# Controller_Board.net
KiCad netlist of a schematic drawn in EAGLE
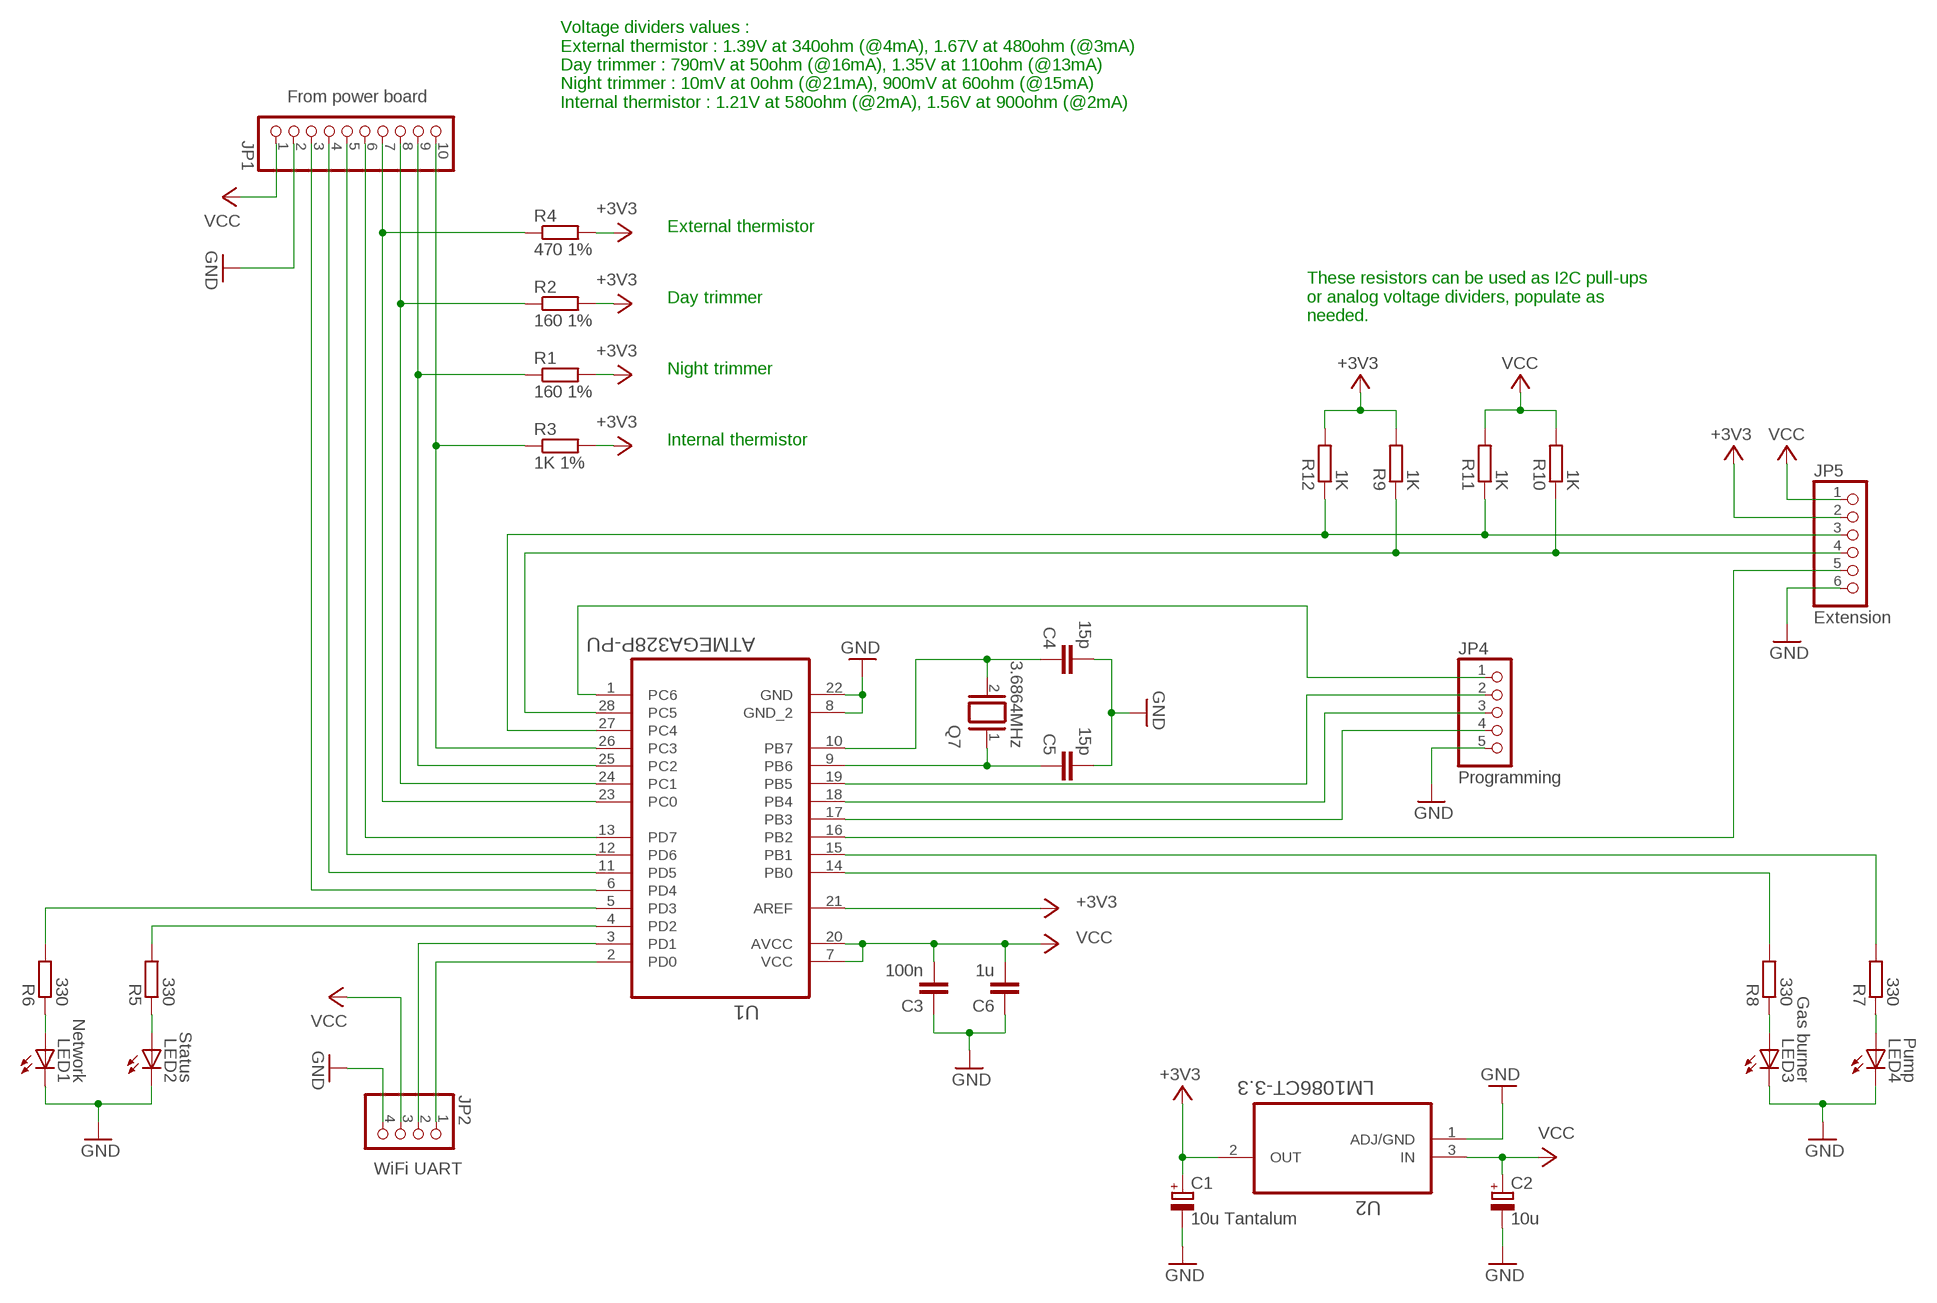
[diagram p0: schematic, sheet 1]

(export (version "E")
  (design (tool "Eeschema 10.0.6"))
  (components
    (comp (ref "C1")
      (value "10u Tantalum")
      (footprint "eagle-import:E2,5-7")
      (libsource (lib "eagle-import") (part "CPOL-EUE2.5-7"))
    )
    (comp (ref "C2")
      (value "10u")
      (footprint "eagle-import:E2,5-7")
      (libsource (lib "eagle-import") (part "CPOL-EUE2.5-7"))
    )
    (comp (ref "C3")
      (value "100n")
      (footprint "eagle-import:C050-035X075")
      (libsource (lib "eagle-import") (part "C-EU050-035X075"))
    )
    (comp (ref "C4")
      (value "15p")
      (footprint "eagle-import:C025-050X050")
      (libsource (lib "eagle-import") (part "rcl_334_C-EU025-050X050"))
    )
    (comp (ref "C5")
      (value "15p")
      (footprint "eagle-import:C025-050X050")
      (libsource (lib "eagle-import") (part "rcl_334_C-EU025-050X050"))
    )
    (comp (ref "C6")
      (value "1u")
      (footprint "eagle-import:C050-035X075")
      (libsource (lib "eagle-import") (part "C-EU050-035X075"))
    )
    (comp (ref "JP1")
      (value "From power board")
      (footprint "eagle-import:1X10")
      (libsource (lib "eagle-import") (part "PINHD-1X10"))
    )
    (comp (ref "JP2")
      (value "WiFi UART")
      (footprint "eagle-import:1X04")
      (libsource (lib "eagle-import") (part "PINHD-1X4"))
    )
    (comp (ref "JP4")
      (value "Programming")
      (footprint "eagle-import:1X05")
      (libsource (lib "eagle-import") (part "PINHD-1X5"))
    )
    (comp (ref "JP5")
      (value "Extension")
      (footprint "eagle-import:1X06")
      (libsource (lib "eagle-import") (part "PINHD-1X6"))
    )
    (comp (ref "LED1")
      (value "Network")
      (footprint "eagle-import:LED5MM")
      (libsource (lib "eagle-import") (part "LED5MM"))
    )
    (comp (ref "LED2")
      (value "Status")
      (footprint "eagle-import:LED5MM")
      (libsource (lib "eagle-import") (part "LED5MM"))
    )
    (comp (ref "LED3")
      (value "Gas burner")
      (footprint "eagle-import:LED5MM")
      (libsource (lib "eagle-import") (part "LED5MM"))
    )
    (comp (ref "LED4")
      (value "Pump")
      (footprint "eagle-import:LED5MM")
      (libsource (lib "eagle-import") (part "LED5MM"))
    )
    (comp (ref "Q7")
      (value "3.6864MHz")
      (footprint "eagle-import:QS")
      (libsource (lib "eagle-import") (part "XTAL/S"))
    )
    (comp (ref "R1")
      (value "160 1%")
      (footprint "eagle-import:0207_10")
      (libsource (lib "eagle-import") (part "R-EU_0207/10"))
    )
    (comp (ref "R2")
      (value "160 1%")
      (footprint "eagle-import:0207_10")
      (libsource (lib "eagle-import") (part "R-EU_0207/10"))
    )
    (comp (ref "R3")
      (value "1K 1%")
      (footprint "eagle-import:0207_10")
      (libsource (lib "eagle-import") (part "R-EU_0207/10"))
    )
    (comp (ref "R4")
      (value "470 1%")
      (footprint "eagle-import:0207_10")
      (libsource (lib "eagle-import") (part "R-EU_0207/10"))
    )
    (comp (ref "R5")
      (value "330")
      (footprint "eagle-import:0207_10")
      (libsource (lib "eagle-import") (part "R-EU_0207/10"))
    )
    (comp (ref "R6")
      (value "330")
      (footprint "eagle-import:0207_10")
      (libsource (lib "eagle-import") (part "R-EU_0207/10"))
    )
    (comp (ref "R7")
      (value "330")
      (footprint "eagle-import:0207_10")
      (libsource (lib "eagle-import") (part "R-EU_0207/10"))
    )
    (comp (ref "R8")
      (value "330")
      (footprint "eagle-import:0207_10")
      (libsource (lib "eagle-import") (part "R-EU_0207/10"))
    )
    (comp (ref "R9")
      (value "1K")
      (footprint "eagle-import:0207_10")
      (libsource (lib "eagle-import") (part "R-EU_0207/10"))
    )
    (comp (ref "R10")
      (value "1K")
      (footprint "eagle-import:0207_10")
      (libsource (lib "eagle-import") (part "R-EU_0207/10"))
    )
    (comp (ref "R11")
      (value "1K")
      (footprint "eagle-import:0207_10")
      (libsource (lib "eagle-import") (part "R-EU_0207/10"))
    )
    (comp (ref "R12")
      (value "1K")
      (footprint "eagle-import:0207_10")
      (libsource (lib "eagle-import") (part "R-EU_0207/10"))
    )
    (comp (ref "U1")
      (value "ATMEGA328P-PU")
      (footprint "eagle-import:DIP254P762X457-28")
      (libsource (lib "eagle-import") (part "ATMEGA328P-PU"))
    )
    (comp (ref "U2")
      (value "LM1086CT-3.3")
      (footprint "eagle-import:TO254P470X1016X2222-3P")
      (libsource (lib "eagle-import") (part "LM1086CT-3.3"))
    )
  )
  (nets
    (net (code "1") (name "+3V3") (class "Default")
      (node (ref "C1") (pin "+") (pinfunction "+_+") (pintype "passive"))
      (node (ref "JP5") (pin "2") (pinfunction "2_2") (pintype "passive"))
      (node (ref "R1") (pin "2") (pinfunction "2_2") (pintype "passive"))
      (node (ref "R12") (pin "2") (pinfunction "2_2") (pintype "passive"))
      (node (ref "R2") (pin "2") (pinfunction "2_2") (pintype "passive"))
      (node (ref "R3") (pin "2") (pinfunction "2_2") (pintype "passive"))
      (node (ref "R4") (pin "2") (pinfunction "2_2") (pintype "passive"))
      (node (ref "R9") (pin "2") (pinfunction "2_2") (pintype "passive"))
      (node (ref "U1") (pin "21") (pinfunction "AREF_21") (pintype "input"))
      (node (ref "U2") (pin "2") (pinfunction "OUT_2") (pintype "passive"))
    )
    (net (code "2") (name "GND") (class "Default")
      (node (ref "C1") (pin "-") (pinfunction "-_-") (pintype "passive"))
      (node (ref "C2") (pin "-") (pinfunction "-_-") (pintype "passive"))
      (node (ref "C3") (pin "1") (pinfunction "1_1") (pintype "passive"))
      (node (ref "C4") (pin "2") (pinfunction "2_2") (pintype "passive"))
      (node (ref "C5") (pin "2") (pinfunction "2_2") (pintype "passive"))
      (node (ref "C6") (pin "1") (pinfunction "1_1") (pintype "passive"))
      (node (ref "JP1") (pin "2") (pinfunction "2_2") (pintype "passive"))
      (node (ref "JP2") (pin "4") (pinfunction "4_4") (pintype "passive"))
      (node (ref "JP4") (pin "5") (pinfunction "5_5") (pintype "passive"))
      (node (ref "JP5") (pin "6") (pinfunction "6_6") (pintype "passive"))
      (node (ref "LED1") (pin "K") (pinfunction "C_K") (pintype "passive"))
      (node (ref "LED2") (pin "K") (pinfunction "C_K") (pintype "passive"))
      (node (ref "LED3") (pin "K") (pinfunction "C_K") (pintype "passive"))
      (node (ref "LED4") (pin "K") (pinfunction "C_K") (pintype "passive"))
      (node (ref "U1") (pin "22") (pinfunction "GND_22") (pintype "passive"))
      (node (ref "U1") (pin "8") (pinfunction "GND_2_8") (pintype "passive"))
      (node (ref "U2") (pin "1") (pinfunction "ADJ/GND_1") (pintype "passive"))
    )
    (net (code "3") (name "Net-(LED1-PadA)") (class "Default")
      (node (ref "LED1") (pin "A") (pinfunction "A_A") (pintype "passive"))
      (node (ref "R6") (pin "1") (pinfunction "1_1") (pintype "passive"))
    )
    (net (code "4") (name "Net-(LED2-PadA)") (class "Default")
      (node (ref "LED2") (pin "A") (pinfunction "A_A") (pintype "passive"))
      (node (ref "R5") (pin "1") (pinfunction "1_1") (pintype "passive"))
    )
    (net (code "5") (name "Net-(LED3-PadA)") (class "Default")
      (node (ref "LED3") (pin "A") (pinfunction "A_A") (pintype "passive"))
      (node (ref "R8") (pin "1") (pinfunction "1_1") (pintype "passive"))
    )
    (net (code "6") (name "Net-(LED4-PadA)") (class "Default")
      (node (ref "LED4") (pin "A") (pinfunction "A_A") (pintype "passive"))
      (node (ref "R7") (pin "1") (pinfunction "1_1") (pintype "passive"))
    )
    (net (code "7") (name "Net-(U1-PB0)") (class "Default")
      (node (ref "R8") (pin "2") (pinfunction "2_2") (pintype "passive"))
      (node (ref "U1") (pin "14") (pinfunction "PB0_14") (pintype "bidirectional"))
    )
    (net (code "8") (name "Net-(U1-PB1)") (class "Default")
      (node (ref "R7") (pin "2") (pinfunction "2_2") (pintype "passive"))
      (node (ref "U1") (pin "15") (pinfunction "PB1_15") (pintype "bidirectional"))
    )
    (net (code "9") (name "Net-(U1-PB2)") (class "Default")
      (node (ref "JP5") (pin "5") (pinfunction "5_5") (pintype "passive"))
      (node (ref "U1") (pin "16") (pinfunction "PB2_16") (pintype "bidirectional"))
    )
    (net (code "10") (name "Net-(U1-PB3)") (class "Default")
      (node (ref "JP4") (pin "4") (pinfunction "4_4") (pintype "passive"))
      (node (ref "U1") (pin "17") (pinfunction "PB3_17") (pintype "bidirectional"))
    )
    (net (code "11") (name "Net-(U1-PB4)") (class "Default")
      (node (ref "JP4") (pin "3") (pinfunction "3_3") (pintype "passive"))
      (node (ref "U1") (pin "18") (pinfunction "PB4_18") (pintype "bidirectional"))
    )
    (net (code "12") (name "Net-(U1-PB5)") (class "Default")
      (node (ref "JP4") (pin "2") (pinfunction "2_2") (pintype "passive"))
      (node (ref "U1") (pin "19") (pinfunction "PB5_19") (pintype "bidirectional"))
    )
    (net (code "13") (name "Net-(U1-PB6)") (class "Default")
      (node (ref "C5") (pin "1") (pinfunction "1_1") (pintype "passive"))
      (node (ref "Q7") (pin "1") (pinfunction "1_1") (pintype "passive"))
      (node (ref "U1") (pin "9") (pinfunction "PB6_9") (pintype "bidirectional"))
    )
    (net (code "14") (name "Net-(U1-PB7)") (class "Default")
      (node (ref "C4") (pin "1") (pinfunction "1_1") (pintype "passive"))
      (node (ref "Q7") (pin "2") (pinfunction "2_2") (pintype "passive"))
      (node (ref "U1") (pin "10") (pinfunction "PB7_10") (pintype "bidirectional"))
    )
    (net (code "15") (name "Net-(U1-PC0)") (class "Default")
      (node (ref "JP1") (pin "7") (pinfunction "7_7") (pintype "passive"))
      (node (ref "R4") (pin "1") (pinfunction "1_1") (pintype "passive"))
      (node (ref "U1") (pin "23") (pinfunction "PC0_23") (pintype "bidirectional"))
    )
    (net (code "16") (name "Net-(U1-PC1)") (class "Default")
      (node (ref "JP1") (pin "8") (pinfunction "8_8") (pintype "passive"))
      (node (ref "R2") (pin "1") (pinfunction "1_1") (pintype "passive"))
      (node (ref "U1") (pin "24") (pinfunction "PC1_24") (pintype "bidirectional"))
    )
    (net (code "17") (name "Net-(U1-PC2)") (class "Default")
      (node (ref "JP1") (pin "9") (pinfunction "9_9") (pintype "passive"))
      (node (ref "R1") (pin "1") (pinfunction "1_1") (pintype "passive"))
      (node (ref "U1") (pin "25") (pinfunction "PC2_25") (pintype "bidirectional"))
    )
    (net (code "18") (name "Net-(U1-PC3)") (class "Default")
      (node (ref "JP1") (pin "10") (pinfunction "10_10") (pintype "passive"))
      (node (ref "R3") (pin "1") (pinfunction "1_1") (pintype "passive"))
      (node (ref "U1") (pin "26") (pinfunction "PC3_26") (pintype "bidirectional"))
    )
    (net (code "19") (name "Net-(U1-PC4)") (class "Default")
      (node (ref "JP5") (pin "3") (pinfunction "3_3") (pintype "passive"))
      (node (ref "R11") (pin "1") (pinfunction "1_1") (pintype "passive"))
      (node (ref "R12") (pin "1") (pinfunction "1_1") (pintype "passive"))
      (node (ref "U1") (pin "27") (pinfunction "PC4_27") (pintype "bidirectional"))
    )
    (net (code "20") (name "Net-(U1-PC5)") (class "Default")
      (node (ref "JP5") (pin "4") (pinfunction "4_4") (pintype "passive"))
      (node (ref "R10") (pin "1") (pinfunction "1_1") (pintype "passive"))
      (node (ref "R9") (pin "1") (pinfunction "1_1") (pintype "passive"))
      (node (ref "U1") (pin "28") (pinfunction "PC5_28") (pintype "bidirectional"))
    )
    (net (code "21") (name "Net-(U1-PC6)") (class "Default")
      (node (ref "JP4") (pin "1") (pinfunction "1_1") (pintype "passive"))
      (node (ref "U1") (pin "1") (pinfunction "PC6_1") (pintype "bidirectional"))
    )
    (net (code "22") (name "Net-(U1-PD0)") (class "Default")
      (node (ref "JP2") (pin "1") (pinfunction "1_1") (pintype "passive"))
      (node (ref "U1") (pin "2") (pinfunction "PD0_2") (pintype "bidirectional"))
    )
    (net (code "23") (name "Net-(U1-PD1)") (class "Default")
      (node (ref "JP2") (pin "2") (pinfunction "2_2") (pintype "passive"))
      (node (ref "U1") (pin "3") (pinfunction "PD1_3") (pintype "bidirectional"))
    )
    (net (code "24") (name "Net-(U1-PD2)") (class "Default")
      (node (ref "R5") (pin "2") (pinfunction "2_2") (pintype "passive"))
      (node (ref "U1") (pin "4") (pinfunction "PD2_4") (pintype "bidirectional"))
    )
    (net (code "25") (name "Net-(U1-PD3)") (class "Default")
      (node (ref "R6") (pin "2") (pinfunction "2_2") (pintype "passive"))
      (node (ref "U1") (pin "5") (pinfunction "PD3_5") (pintype "bidirectional"))
    )
    (net (code "26") (name "Net-(U1-PD4)") (class "Default")
      (node (ref "JP1") (pin "3") (pinfunction "3_3") (pintype "passive"))
      (node (ref "U1") (pin "6") (pinfunction "PD4_6") (pintype "bidirectional"))
    )
    (net (code "27") (name "Net-(U1-PD5)") (class "Default")
      (node (ref "JP1") (pin "4") (pinfunction "4_4") (pintype "passive"))
      (node (ref "U1") (pin "11") (pinfunction "PD5_11") (pintype "bidirectional"))
    )
    (net (code "28") (name "Net-(U1-PD6)") (class "Default")
      (node (ref "JP1") (pin "5") (pinfunction "5_5") (pintype "passive"))
      (node (ref "U1") (pin "12") (pinfunction "PD6_12") (pintype "bidirectional"))
    )
    (net (code "29") (name "Net-(U1-PD7)") (class "Default")
      (node (ref "JP1") (pin "6") (pinfunction "6_6") (pintype "passive"))
      (node (ref "U1") (pin "13") (pinfunction "PD7_13") (pintype "bidirectional"))
    )
    (net (code "30") (name "VCC") (class "Default")
      (node (ref "C2") (pin "+") (pinfunction "+_+") (pintype "passive"))
      (node (ref "C3") (pin "2") (pinfunction "2_2") (pintype "passive"))
      (node (ref "C6") (pin "2") (pinfunction "2_2") (pintype "passive"))
      (node (ref "JP1") (pin "1") (pinfunction "1_1") (pintype "passive"))
      (node (ref "JP2") (pin "3") (pinfunction "3_3") (pintype "passive"))
      (node (ref "JP5") (pin "1") (pinfunction "1_1") (pintype "passive"))
      (node (ref "R10") (pin "2") (pinfunction "2_2") (pintype "passive"))
      (node (ref "R11") (pin "2") (pinfunction "2_2") (pintype "passive"))
      (node (ref "U1") (pin "20") (pinfunction "AVCC_20") (pintype "power_in"))
      (node (ref "U1") (pin "7") (pinfunction "VCC_7") (pintype "power_in"))
      (node (ref "U2") (pin "3") (pinfunction "IN_3") (pintype "input"))
    )
  )
)
